# Battery_Mnitor.net
KiCad netlist of a schematic drawn in Altium Designer
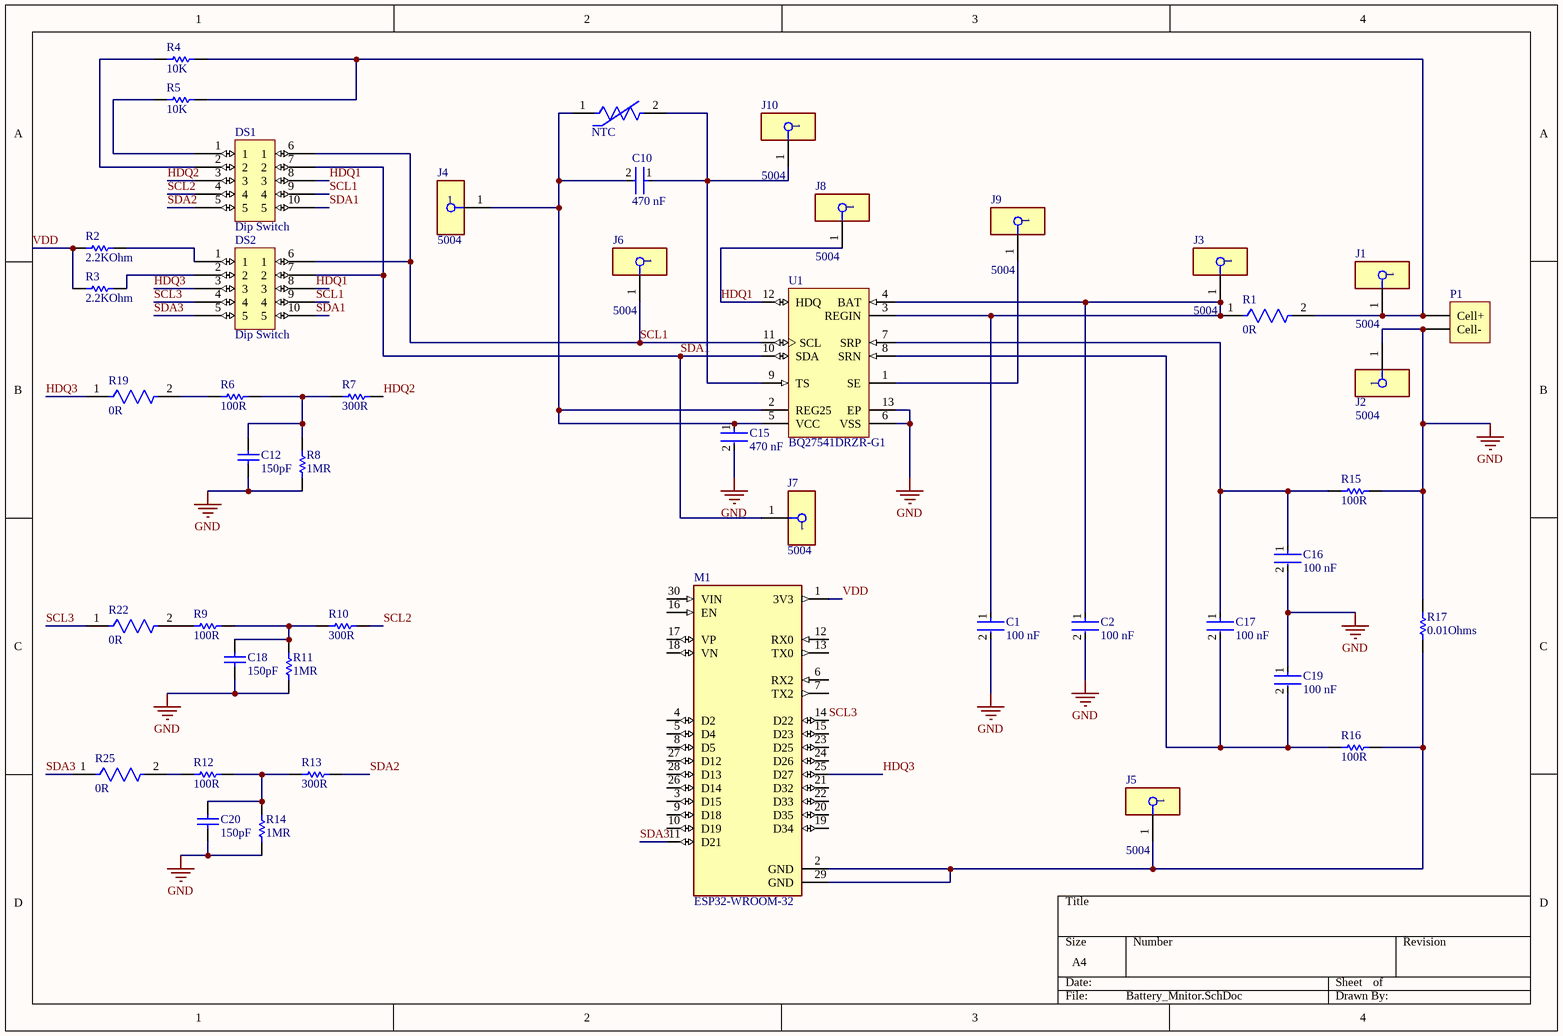
[diagram p0: Battery_Mnitor.SchDoc]

(export (version "E")
  (design (tool "Eeschema 10.0.6"))
  (components
    (comp (ref "C1")
      (value "100 nF")
      (footprint "FP-CC0402-MFG")
      (description "CC0402 100 nF X7R 10.00% 16 V")
      (fields (field (name "MANUFACTURER") "YAGEO"))
      (libsource (lib "Altium Content Vault") (part "11868f565c42a9108669ba33697ecf6"))
    )
    (comp (ref "C2")
      (value "100 nF")
      (footprint "FP-CC0402-MFG")
      (description "CC0402 100 nF X7R 10.00% 16 V")
      (fields (field (name "MANUFACTURER") "YAGEO"))
      (libsource (lib "Altium Content Vault") (part "11868f565c42a9108669ba33697ecf6"))
    )
    (comp (ref "C10")
      (value "470 nF")
      (footprint "FP-CC0402-MFG")
      (description "CC0402 470 nF X5R 10.00% 25 V")
      (fields (field (name "TOLERANCE") "0.1") (field (name "MANUFACTURER") "YAGEO"))
      (libsource (lib "Altium Content Vault") (part "11868f565c42a9108669ba33697ecf6"))
    )
    (comp (ref "C12")
      (value "150pF")
      (footprint "CAPC1005X55X25LL05T10")
      (description "50V 150pF C0G ±5% 0402 Multilayer Ceramic Capacitors MLCC - SMD/SMT ROHS")
      (fields (field (name "MANUFACTURER") "Murata") (field (name "MFR. PART #") "GRM1555C1H151JA01D"))
      (libsource (lib "Altium Content Vault") (part "CAP"))
    )
    (comp (ref "C15")
      (value "470 nF")
      (footprint "FP-CC0402-MFG")
      (description "CC0402 470 nF X5R 10.00% 25 V")
      (fields (field (name "TOLERANCE") "0.1") (field (name "MANUFACTURER") "YAGEO"))
      (libsource (lib "Altium Content Vault") (part "11868f565c42a9108669ba33697ecf6"))
    )
    (comp (ref "C16")
      (value "100 nF")
      (footprint "FP-CC0402-MFG")
      (description "CC0402 100 nF X7R 10.00% 16 V")
      (fields (field (name "MANUFACTURER") "YAGEO"))
      (libsource (lib "Altium Content Vault") (part "11868f565c42a9108669ba33697ecf6"))
    )
    (comp (ref "C17")
      (value "100 nF")
      (footprint "FP-CC0402-MFG")
      (description "CC0402 100 nF X7R 10.00% 16 V")
      (fields (field (name "MANUFACTURER") "YAGEO"))
      (libsource (lib "Altium Content Vault") (part "11868f565c42a9108669ba33697ecf6"))
    )
    (comp (ref "C18")
      (value "150pF")
      (footprint "CAPC1005X55X25LL05T10")
      (description "50V 150pF C0G ±5% 0402 Multilayer Ceramic Capacitors MLCC - SMD/SMT ROHS")
      (fields (field (name "MANUFACTURER") "Murata") (field (name "MFR. PART #") "GRM1555C1H151JA01D"))
      (libsource (lib "Altium Content Vault") (part "CAP"))
    )
    (comp (ref "C19")
      (value "100 nF")
      (footprint "FP-CC0402-MFG")
      (description "CC0402 100 nF X7R 10.00% 16 V")
      (fields (field (name "MANUFACTURER") "YAGEO"))
      (libsource (lib "Altium Content Vault") (part "11868f565c42a9108669ba33697ecf6"))
    )
    (comp (ref "C20")
      (value "150pF")
      (footprint "CAPC1005X55X25LL05T10")
      (description "50V 150pF C0G ±5% 0402 Multilayer Ceramic Capacitors MLCC - SMD/SMT ROHS")
      (fields (field (name "MANUFACTURER") "Murata") (field (name "MFR. PART #") "GRM1555C1H151JA01D"))
      (libsource (lib "Altium Content Vault") (part "CAP"))
    )
    (comp (ref "DS1")
      (value "Dip Switch")
      (footprint "DIP10")
      (description "SPST 24V 25mA Red -20℃~+70℃ 3000 Flat dial, raised type 2.54mm 6 Plugin DIP Switches ROHS")
      (fields (field (name "LCSC PART #") "C129061") (field (name "MANUFACTURER") "Korean Hroparts Elec"))
      (libsource (lib "Dip switch") (part "DS-05RP"))
    )
    (comp (ref "DS2")
      (value "Dip Switch")
      (footprint "DIP10")
      (description "SPST 24V 25mA Red -20℃~+70℃ 3000 Flat dial, raised type 2.54mm 6 Plugin DIP Switches ROHS")
      (fields (field (name "LCSC PART #") "C129061") (field (name "MANUFACTURER") "Korean Hroparts Elec"))
      (libsource (lib "Dip switch") (part "DS-05RP"))
    )
    (comp (ref "J1")
      (value "5004")
      (footprint "FP-5004-MFG")
      (description "PC TEST POINT MINIATURE YELLOW")
      (fields
        (field (name "MANUFACTURER") "Keystone")
        (field (name "OCTOPART") "https://octopart.com/5004-keystone-28591")
      )
      (libsource (lib "Altium Content Vault") (part "98815daf2f2c152b0c43f5ab9800df6"))
    )
    (comp (ref "J2")
      (value "5004")
      (footprint "FP-5004-MFG")
      (description "PC TEST POINT MINIATURE YELLOW")
      (fields
        (field (name "MANUFACTURER") "Keystone")
        (field (name "OCTOPART") "https://octopart.com/5004-keystone-28591")
      )
      (libsource (lib "") (part "98815daf2f2c152b0c43f5ab9800df6_2"))
    )
    (comp (ref "J3")
      (value "5004")
      (footprint "FP-5004-MFG")
      (description "PC TEST POINT MINIATURE YELLOW")
      (fields
        (field (name "MANUFACTURER") "Keystone")
        (field (name "OCTOPART") "https://octopart.com/5004-keystone-28591")
      )
      (libsource (lib "Altium Content Vault") (part "98815daf2f2c152b0c43f5ab9800df6"))
    )
    (comp (ref "J4")
      (value "5004")
      (footprint "FP-5004-MFG")
      (description "PC TEST POINT MINIATURE YELLOW")
      (fields
        (field (name "MANUFACTURER") "Keystone")
        (field (name "OCTOPART") "https://octopart.com/5004-keystone-28591")
      )
      (libsource (lib "") (part "98815daf2f2c152b0c43f5ab9800df6_3"))
    )
    (comp (ref "J5")
      (value "5004")
      (footprint "FP-5004-MFG")
      (description "PC TEST POINT MINIATURE YELLOW")
      (fields
        (field (name "MANUFACTURER") "Keystone")
        (field (name "OCTOPART") "https://octopart.com/5004-keystone-28591")
      )
      (libsource (lib "Altium Content Vault") (part "98815daf2f2c152b0c43f5ab9800df6"))
    )
    (comp (ref "J6")
      (value "5004")
      (footprint "FP-5004-MFG")
      (description "PC TEST POINT MINIATURE YELLOW")
      (fields
        (field (name "MANUFACTURER") "Keystone")
        (field (name "OCTOPART") "https://octopart.com/5004-keystone-28591")
      )
      (libsource (lib "Altium Content Vault") (part "98815daf2f2c152b0c43f5ab9800df6"))
    )
    (comp (ref "J7")
      (value "5004")
      (footprint "FP-5004-MFG")
      (description "PC TEST POINT MINIATURE YELLOW")
      (fields
        (field (name "MANUFACTURER") "Keystone")
        (field (name "OCTOPART") "https://octopart.com/5004-keystone-28591")
      )
      (libsource (lib "") (part "98815daf2f2c152b0c43f5ab9800df6_1"))
    )
    (comp (ref "J8")
      (value "5004")
      (footprint "FP-5004-MFG")
      (description "PC TEST POINT MINIATURE YELLOW")
      (fields
        (field (name "MANUFACTURER") "Keystone")
        (field (name "OCTOPART") "https://octopart.com/5004-keystone-28591")
      )
      (libsource (lib "Altium Content Vault") (part "98815daf2f2c152b0c43f5ab9800df6"))
    )
    (comp (ref "J9")
      (value "5004")
      (footprint "FP-5004-MFG")
      (description "PC TEST POINT MINIATURE YELLOW")
      (fields
        (field (name "MANUFACTURER") "Keystone")
        (field (name "OCTOPART") "https://octopart.com/5004-keystone-28591")
      )
      (libsource (lib "Altium Content Vault") (part "98815daf2f2c152b0c43f5ab9800df6"))
    )
    (comp (ref "J10")
      (value "5004")
      (footprint "FP-5004-MFG")
      (description "PC TEST POINT MINIATURE YELLOW")
      (fields
        (field (name "MANUFACTURER") "Keystone")
        (field (name "OCTOPART") "https://octopart.com/5004-keystone-28591")
      )
      (libsource (lib "Altium Content Vault") (part "98815daf2f2c152b0c43f5ab9800df6"))
    )
    (comp (ref "M1")
      (value "ESP32-WROOM-32")
      (footprint "ESP32-DEVKIT-V1")
      (libsource (lib "Modules") (part "ESP32-DEVKIT-V1"))
    )
    (comp (ref "NTC")
      (value "NXRT15XH103FA1B030")
      (footprint "FP-NXR_151B030-MFG")
      (description "Thermistor NTC 10kΩ ±1% 2-Pin Radial Bulk")
      (fields (field (name "TOLERANCE") "1%") (field (name "LCSC PART #") "C152559"))
      (libsource (lib "Altium Content Vault") (part "3b148a6ebabc5fb4d708a66c052d352"))
    )
    (comp (ref "P1")
      (value "Header 2H")
      (footprint "HDR1X2H")
      (description "Header, 2-Pin, Right Angle")
      (fields (field (name "PUBLISHER") "Altium Limited"))
      (libsource (lib "Miscellaneous Connectors") (part "Header 2H"))
    )
    (comp (ref "R1")
      (value "0R")
      (footprint "FP-RC0402-0_4-IPC_A")
      (description "RES SMD 0 OHM JUMPER 1/16W 0402")
      (fields (field (name "TOLERANCE") "1%") (field (name "LCSC PART #") "C106231"))
      (libsource (lib "Altium Content Vault") (part "1029c3af85768c4190bb7ad29bc67b5"))
    )
    (comp (ref "R2")
      (value "2.2KOhm")
      (footprint "RESC3116X65X40ML10T20")
      (description "Chip Resistor, 2.2 KOhm, +/- 1%, 250 mW, -55 to 155 degC, 1206 (3216 Metric), RoHS, Tape and Reel")
      (fields (field (name "MANUFACTURER") "Yageo") (field (name "TOLERANCE") "1%"))
      (libsource (lib "Altium Content Vault") (part "RES-2"))
    )
    (comp (ref "R3")
      (value "2.2KOhm")
      (footprint "RESC3116X65X40ML10T20")
      (description "Chip Resistor, 2.2 KOhm, +/- 1%, 250 mW, -55 to 155 degC, 1206 (3216 Metric), RoHS, Tape and Reel")
      (fields (field (name "MANUFACTURER") "Yageo") (field (name "TOLERANCE") "1%"))
      (libsource (lib "Altium Content Vault") (part "RES-2"))
    )
    (comp (ref "R4")
      (value "10K")
      (footprint "RESC1005X40X25LL05T10")
      (fields
        (field (name "MANUFACTURER") "Yageo / Phycomp")
        (field (name "LCSC PART #") "C60490")
        (field (name "MFR. PART #") "RC0402FR-0710KL")
      )
      (libsource (lib "Altium Content Vault") (part "RES"))
    )
    (comp (ref "R5")
      (value "10K")
      (footprint "RESC1005X40X25LL05T10")
      (fields
        (field (name "MANUFACTURER") "Yageo / Phycomp")
        (field (name "LCSC PART #") "C60490")
        (field (name "MFR. PART #") "RC0402FR-0710KL")
      )
      (libsource (lib "Altium Content Vault") (part "RES"))
    )
    (comp (ref "R6")
      (value "100R")
      (footprint "RESC1005X40X25ML05T10")
      (fields
        (field (name "MFR. PART #") "RC0402FR-07100RL")
        (field (name "MANUFACTURER") "Yageo / Phycomp")
        (field (name "LCSC PART #") "C106232")
      )
      (libsource (lib "Altium Content Vault") (part "RES"))
    )
    (comp (ref "R7")
      (value "300R")
      (footprint "RESC1005X40X25LL05T10")
      (fields
        (field (name "MFR. PART #") "RC0402FR-07300RL")
        (field (name "MANUFACTURER") "Yageo / Phycomp")
        (field (name "LCSC PART #") "C138010")
      )
      (libsource (lib "Altium Content Vault") (part "RES"))
    )
    (comp (ref "R8")
      (value "1MR")
      (footprint "RESC1005X40X25NL05T10")
      (description "62.5mW 50V ±100ppm/℃ ±1% -55℃~+155℃ 1MΩ 0402 Chip Resistor - Surface Mount ROHS")
      (fields (field (name "MANUFACTURER") "Yageo / Phycomp") (field (name "MFR. PART #") "RC0402FR-071ML"))
      (libsource (lib "Altium Content Vault") (part "RES"))
    )
    (comp (ref "R9")
      (value "100R")
      (footprint "RESC1005X40X25ML05T10")
      (fields
        (field (name "MFR. PART #") "RC0402FR-07100RL")
        (field (name "MANUFACTURER") "Yageo / Phycomp")
        (field (name "LCSC PART #") "C106232")
      )
      (libsource (lib "Altium Content Vault") (part "RES"))
    )
    (comp (ref "R10")
      (value "300R")
      (footprint "RESC1005X40X25LL05T10")
      (fields
        (field (name "MFR. PART #") "RC0402FR-07300RL")
        (field (name "MANUFACTURER") "Yageo / Phycomp")
        (field (name "LCSC PART #") "C138010")
      )
      (libsource (lib "Altium Content Vault") (part "RES"))
    )
    (comp (ref "R11")
      (value "1MR")
      (footprint "RESC1005X40X25NL05T10")
      (description "62.5mW 50V ±100ppm/℃ ±1% -55℃~+155℃ 1MΩ 0402 Chip Resistor - Surface Mount ROHS")
      (fields (field (name "MANUFACTURER") "Yageo / Phycomp") (field (name "MFR. PART #") "RC0402FR-071ML"))
      (libsource (lib "Altium Content Vault") (part "RES"))
    )
    (comp (ref "R12")
      (value "100R")
      (footprint "RESC1005X40X25ML05T10")
      (fields
        (field (name "MFR. PART #") "RC0402FR-07100RL")
        (field (name "MANUFACTURER") "Yageo / Phycomp")
        (field (name "LCSC PART #") "C106232")
      )
      (libsource (lib "Altium Content Vault") (part "RES"))
    )
    (comp (ref "R13")
      (value "300R")
      (footprint "RESC1005X40X25LL05T10")
      (fields
        (field (name "MFR. PART #") "RC0402FR-07300RL")
        (field (name "MANUFACTURER") "Yageo / Phycomp")
        (field (name "LCSC PART #") "C138010")
      )
      (libsource (lib "Altium Content Vault") (part "RES"))
    )
    (comp (ref "R14")
      (value "1MR")
      (footprint "RESC1005X40X25NL05T10")
      (description "62.5mW 50V ±100ppm/℃ ±1% -55℃~+155℃ 1MΩ 0402 Chip Resistor - Surface Mount ROHS")
      (fields (field (name "MANUFACTURER") "Yageo / Phycomp") (field (name "MFR. PART #") "RC0402FR-071ML"))
      (libsource (lib "Altium Content Vault") (part "RES"))
    )
    (comp (ref "R15")
      (value "100R")
      (footprint "RESC1005X40X25ML05T10")
      (fields
        (field (name "MFR. PART #") "RC0402FR-07100RL")
        (field (name "MANUFACTURER") "Yageo / Phycomp")
        (field (name "LCSC PART #") "C106232")
      )
      (libsource (lib "Altium Content Vault") (part "RES"))
    )
    (comp (ref "R16")
      (value "100R")
      (footprint "RESC1005X40X25ML05T10")
      (fields
        (field (name "MFR. PART #") "RC0402FR-07100RL")
        (field (name "MANUFACTURER") "Yageo / Phycomp")
        (field (name "LCSC PART #") "C106232")
      )
      (libsource (lib "Altium Content Vault") (part "RES"))
    )
    (comp (ref "R17")
      (value "0.01Ohms")
      (footprint "RESC5125X89X51LL25T25")
      (description "Chip Resistor, 10 mOhm, +/- 1%, 0.5 W, -65 to 170 degC, 2010 (5025 Metric), RoHS, Tape and Reel")
      (fields (field (name "MANUFACTURER") "Vishay") (field (name "TOLERANCE") "1%"))
      (libsource (lib "Altium Content Vault") (part "RES-2"))
    )
    (comp (ref "R19")
      (value "0R")
      (footprint "FP-RC0402-0_4-IPC_A")
      (description "RES SMD 0 OHM JUMPER 1/16W 0402")
      (fields (field (name "TOLERANCE") "1%") (field (name "LCSC PART #") "C106231"))
      (libsource (lib "Altium Content Vault") (part "1029c3af85768c4190bb7ad29bc67b5"))
    )
    (comp (ref "R22")
      (value "0R")
      (footprint "FP-RC0402-0_4-IPC_A")
      (description "RES SMD 0 OHM JUMPER 1/16W 0402")
      (fields (field (name "TOLERANCE") "1%") (field (name "LCSC PART #") "C106231"))
      (libsource (lib "Altium Content Vault") (part "1029c3af85768c4190bb7ad29bc67b5"))
    )
    (comp (ref "R25")
      (value "0R")
      (footprint "FP-RC0402-0_4-IPC_A")
      (description "RES SMD 0 OHM JUMPER 1/16W 0402")
      (fields (field (name "TOLERANCE") "1%") (field (name "LCSC PART #") "C106231"))
      (libsource (lib "Altium Content Vault") (part "1029c3af85768c4190bb7ad29bc67b5"))
    )
    (comp (ref "U1")
      (value "BQ27541DRZR-G1")
      (footprint "DRZ0012A_V")
      (fields (field (name "MANUFACTURER") "Texas Instruments"))
      (libsource (lib "Altium Content Vault") (part "TI-BQ27541-G1DRZ12-1950X2450TP"))
    )
  )
  (nets
    (net (code "1") (name "/HDQ1") (class "Default")
      (node (ref "DS1") (pin "8") (pinfunction "3_8") (pintype "bidirectional"))
      (node (ref "DS2") (pin "8") (pinfunction "3_8") (pintype "bidirectional"))
      (node (ref "J8") (pin "1") (pinfunction "1_1") (pintype "passive"))
      (node (ref "U1") (pin "12") (pinfunction "HDQ_12") (pintype "bidirectional"))
    )
    (net (code "2") (name "/HDQ2") (class "Default")
      (node (ref "DS1") (pin "3") (pinfunction "3_3") (pintype "bidirectional"))
      (node (ref "R7") (pin "2") (pinfunction "2_2") (pintype "passive"))
    )
    (net (code "3") (name "/HDQ3") (class "Default")
      (node (ref "DS2") (pin "3") (pinfunction "3_3") (pintype "bidirectional"))
      (node (ref "M1") (pin "25") (pinfunction "D27_25") (pintype "bidirectional"))
      (node (ref "R19") (pin "1") (pinfunction "1_1") (pintype "passive"))
    )
    (net (code "4") (name "/SCL1") (class "Default")
      (node (ref "DS1") (pin "6") (pinfunction "1_6") (pintype "bidirectional"))
      (node (ref "DS1") (pin "9") (pinfunction "4_9") (pintype "bidirectional"))
      (node (ref "DS2") (pin "6") (pinfunction "1_6") (pintype "bidirectional"))
      (node (ref "DS2") (pin "9") (pinfunction "4_9") (pintype "bidirectional"))
      (node (ref "J6") (pin "1") (pinfunction "1_1") (pintype "passive"))
      (node (ref "U1") (pin "11") (pinfunction "SCL_11") (pintype "bidirectional"))
    )
    (net (code "5") (name "/SCL2") (class "Default")
      (node (ref "DS1") (pin "4") (pinfunction "4_4") (pintype "bidirectional"))
      (node (ref "R10") (pin "2") (pinfunction "2_2") (pintype "passive"))
    )
    (net (code "6") (name "/SCL3") (class "Default")
      (node (ref "DS2") (pin "4") (pinfunction "4_4") (pintype "bidirectional"))
      (node (ref "M1") (pin "14") (pinfunction "D22_14") (pintype "bidirectional"))
      (node (ref "R22") (pin "1") (pinfunction "1_1") (pintype "passive"))
    )
    (net (code "7") (name "/SDA1") (class "Default")
      (node (ref "DS1") (pin "10") (pinfunction "5_10") (pintype "bidirectional"))
      (node (ref "DS1") (pin "7") (pinfunction "2_7") (pintype "bidirectional"))
      (node (ref "DS2") (pin "10") (pinfunction "5_10") (pintype "bidirectional"))
      (node (ref "DS2") (pin "7") (pinfunction "2_7") (pintype "bidirectional"))
      (node (ref "J7") (pin "1") (pinfunction "1_1") (pintype "passive"))
      (node (ref "U1") (pin "10") (pinfunction "SDA_10") (pintype "bidirectional"))
    )
    (net (code "8") (name "/SDA2") (class "Default")
      (node (ref "DS1") (pin "5") (pinfunction "5_5") (pintype "bidirectional"))
      (node (ref "R13") (pin "2") (pinfunction "2_2") (pintype "passive"))
    )
    (net (code "9") (name "/SDA3") (class "Default")
      (node (ref "DS2") (pin "5") (pinfunction "5_5") (pintype "bidirectional"))
      (node (ref "M1") (pin "11") (pinfunction "D21_11") (pintype "bidirectional"))
      (node (ref "R25") (pin "1") (pinfunction "1_1") (pintype "passive"))
    )
    (net (code "10") (name "/VDD") (class "Default")
      (node (ref "M1") (pin "1") (pinfunction "3V3_1") (pintype "output"))
      (node (ref "R2") (pin "1") (pinfunction "1_1") (pintype "passive"))
      (node (ref "R3") (pin "1") (pinfunction "1_1") (pintype "passive"))
    )
    (net (code "11") (name "GND") (class "Default")
      (node (ref "C1") (pin "2") (pinfunction "2_2") (pintype "passive"))
      (node (ref "C12") (pin "1") (pinfunction "1_1") (pintype "passive"))
      (node (ref "C15") (pin "2") (pinfunction "2_2") (pintype "passive"))
      (node (ref "C16") (pin "2") (pinfunction "2_2") (pintype "passive"))
      (node (ref "C18") (pin "1") (pinfunction "1_1") (pintype "passive"))
      (node (ref "C19") (pin "1") (pinfunction "1_1") (pintype "passive"))
      (node (ref "C2") (pin "2") (pinfunction "2_2") (pintype "passive"))
      (node (ref "C20") (pin "1") (pinfunction "1_1") (pintype "passive"))
      (node (ref "J2") (pin "1") (pinfunction "1_1") (pintype "passive"))
      (node (ref "P1") (pin "2") (pinfunction "Cell-_2") (pintype "passive"))
      (node (ref "R11") (pin "1") (pinfunction "1_1") (pintype "passive"))
      (node (ref "R14") (pin "1") (pinfunction "1_1") (pintype "passive"))
      (node (ref "R15") (pin "2") (pinfunction "2_2") (pintype "passive"))
      (node (ref "R17") (pin "2") (pinfunction "2_2") (pintype "passive"))
      (node (ref "R8") (pin "1") (pinfunction "1_1") (pintype "passive"))
      (node (ref "U1") (pin "13") (pinfunction "EP_13") (pintype "passive"))
      (node (ref "U1") (pin "6") (pinfunction "VSS_6") (pintype "power_in"))
    )
    (net (code "12") (name "Net-(C12-Pad2)") (class "Default")
      (node (ref "C12") (pin "2") (pinfunction "2_2") (pintype "passive"))
      (node (ref "R6") (pin "2") (pinfunction "2_2") (pintype "passive"))
      (node (ref "R7") (pin "1") (pinfunction "1_1") (pintype "passive"))
      (node (ref "R8") (pin "2") (pinfunction "2_2") (pintype "passive"))
    )
    (net (code "13") (name "Net-(C18-Pad2)") (class "Default")
      (node (ref "C18") (pin "2") (pinfunction "2_2") (pintype "passive"))
      (node (ref "R10") (pin "1") (pinfunction "1_1") (pintype "passive"))
      (node (ref "R11") (pin "2") (pinfunction "2_2") (pintype "passive"))
      (node (ref "R9") (pin "2") (pinfunction "2_2") (pintype "passive"))
    )
    (net (code "14") (name "Net-(C20-Pad2)") (class "Default")
      (node (ref "C20") (pin "2") (pinfunction "2_2") (pintype "passive"))
      (node (ref "R12") (pin "2") (pinfunction "2_2") (pintype "passive"))
      (node (ref "R13") (pin "1") (pinfunction "1_1") (pintype "passive"))
      (node (ref "R14") (pin "2") (pinfunction "2_2") (pintype "passive"))
    )
    (net (code "15") (name "Net-(DS1-Pad1)") (class "Default")
      (node (ref "DS1") (pin "1") (pinfunction "1_1") (pintype "bidirectional"))
      (node (ref "R5") (pin "2") (pinfunction "2_2") (pintype "passive"))
    )
    (net (code "16") (name "Net-(DS1-Pad2)") (class "Default")
      (node (ref "DS1") (pin "2") (pinfunction "2_2") (pintype "bidirectional"))
      (node (ref "R4") (pin "2") (pinfunction "2_2") (pintype "passive"))
    )
    (net (code "17") (name "Net-(DS2-Pad1)") (class "Default")
      (node (ref "DS2") (pin "1") (pinfunction "1_1") (pintype "bidirectional"))
      (node (ref "R2") (pin "2") (pinfunction "2_2") (pintype "passive"))
    )
    (net (code "18") (name "Net-(DS2-Pad2)") (class "Default")
      (node (ref "DS2") (pin "2") (pinfunction "2_2") (pintype "bidirectional"))
      (node (ref "R3") (pin "2") (pinfunction "2_2") (pintype "passive"))
    )
    (net (code "19") (name "Net-(J5-Pad1)") (class "Default")
      (node (ref "J5") (pin "1") (pinfunction "1_1") (pintype "passive"))
      (node (ref "M1") (pin "2") (pinfunction "GND_2") (pintype "power_in"))
      (node (ref "M1") (pin "29") (pinfunction "GND_29") (pintype "power_in"))
      (node (ref "R16") (pin "2") (pinfunction "2_2") (pintype "passive"))
      (node (ref "R17") (pin "1") (pinfunction "1_1") (pintype "passive"))
    )
    (net (code "20") (name "Net-(P1-Cell+)") (class "Default")
      (node (ref "J1") (pin "1") (pinfunction "1_1") (pintype "passive"))
      (node (ref "P1") (pin "1") (pinfunction "Cell+_1") (pintype "passive"))
      (node (ref "R1") (pin "2") (pinfunction "2_2") (pintype "passive"))
      (node (ref "R4") (pin "1") (pinfunction "1_1") (pintype "passive"))
      (node (ref "R5") (pin "1") (pinfunction "1_1") (pintype "passive"))
    )
    (net (code "21") (name "Net-(R12-Pad1)") (class "Default")
      (node (ref "R12") (pin "1") (pinfunction "1_1") (pintype "passive"))
      (node (ref "R25") (pin "2") (pinfunction "2_2") (pintype "passive"))
    )
    (net (code "22") (name "Net-(R19-Pad2)") (class "Default")
      (node (ref "R19") (pin "2") (pinfunction "2_2") (pintype "passive"))
      (node (ref "R6") (pin "1") (pinfunction "1_1") (pintype "passive"))
    )
    (net (code "23") (name "Net-(R22-Pad2)") (class "Default")
      (node (ref "R22") (pin "2") (pinfunction "2_2") (pintype "passive"))
      (node (ref "R9") (pin "1") (pinfunction "1_1") (pintype "passive"))
    )
    (net (code "24") (name "Net-(U1-BAT)") (class "Default")
      (node (ref "C1") (pin "1") (pinfunction "1_1") (pintype "passive"))
      (node (ref "C2") (pin "1") (pinfunction "1_1") (pintype "passive"))
      (node (ref "J3") (pin "1") (pinfunction "1_1") (pintype "passive"))
      (node (ref "R1") (pin "1") (pinfunction "1_1") (pintype "passive"))
      (node (ref "U1") (pin "3") (pinfunction "REGIN_3") (pintype "power_in"))
      (node (ref "U1") (pin "4") (pinfunction "BAT_4") (pintype "input"))
    )
    (net (code "25") (name "Net-(U1-REG25)") (class "Default")
      (node (ref "C10") (pin "2") (pinfunction "2_2") (pintype "passive"))
      (node (ref "C15") (pin "1") (pinfunction "1_1") (pintype "passive"))
      (node (ref "J4") (pin "1") (pinfunction "1_1") (pintype "passive"))
      (node (ref "NTC") (pin "1") (pinfunction "1_1") (pintype "passive"))
      (node (ref "U1") (pin "2") (pinfunction "REG25_2") (pintype "power_in"))
      (node (ref "U1") (pin "5") (pinfunction "VCC_5") (pintype "power_in"))
    )
    (net (code "26") (name "Net-(U1-SE)") (class "Default")
      (node (ref "J9") (pin "1") (pinfunction "1_1") (pintype "passive"))
      (node (ref "U1") (pin "1") (pinfunction "SE_1") (pintype "tri_state"))
    )
    (net (code "27") (name "Net-(U1-SRN)") (class "Default")
      (node (ref "C17") (pin "2") (pinfunction "2_2") (pintype "passive"))
      (node (ref "C19") (pin "2") (pinfunction "2_2") (pintype "passive"))
      (node (ref "R16") (pin "1") (pinfunction "1_1") (pintype "passive"))
      (node (ref "U1") (pin "8") (pinfunction "SRN_8") (pintype "input"))
    )
    (net (code "28") (name "Net-(U1-SRP)") (class "Default")
      (node (ref "C16") (pin "1") (pinfunction "1_1") (pintype "passive"))
      (node (ref "C17") (pin "1") (pinfunction "1_1") (pintype "passive"))
      (node (ref "R15") (pin "1") (pinfunction "1_1") (pintype "passive"))
      (node (ref "U1") (pin "7") (pinfunction "SRP_7") (pintype "input"))
    )
    (net (code "29") (name "Net-(U1-TS)") (class "Default")
      (node (ref "C10") (pin "1") (pinfunction "1_1") (pintype "passive"))
      (node (ref "J10") (pin "1") (pinfunction "1_1") (pintype "passive"))
      (node (ref "NTC") (pin "2") (pinfunction "2_2") (pintype "passive"))
      (node (ref "U1") (pin "9") (pinfunction "TS_9") (pintype "input"))
    )
    (net (code "30") (name "unconnected-(M1-D2-Pad4)") (class "Default")
      (node (ref "M1") (pin "4") (pinfunction "D2_4") (pintype "bidirectional"))
    )
    (net (code "31") (name "unconnected-(M1-D4-Pad5)") (class "Default")
      (node (ref "M1") (pin "5") (pinfunction "D4_5") (pintype "bidirectional"))
    )
    (net (code "32") (name "unconnected-(M1-D5-Pad8)") (class "Default")
      (node (ref "M1") (pin "8") (pinfunction "D5_8") (pintype "bidirectional"))
    )
    (net (code "33") (name "unconnected-(M1-D12-Pad27)") (class "Default")
      (node (ref "M1") (pin "27") (pinfunction "D12_27") (pintype "bidirectional"))
    )
    (net (code "34") (name "unconnected-(M1-D13-Pad28)") (class "Default")
      (node (ref "M1") (pin "28") (pinfunction "D13_28") (pintype "bidirectional"))
    )
    (net (code "35") (name "unconnected-(M1-D14-Pad26)") (class "Default")
      (node (ref "M1") (pin "26") (pinfunction "D14_26") (pintype "bidirectional"))
    )
    (net (code "36") (name "unconnected-(M1-D15-Pad3)") (class "Default")
      (node (ref "M1") (pin "3") (pinfunction "D15_3") (pintype "bidirectional"))
    )
    (net (code "37") (name "unconnected-(M1-D18-Pad9)") (class "Default")
      (node (ref "M1") (pin "9") (pinfunction "D18_9") (pintype "bidirectional"))
    )
    (net (code "38") (name "unconnected-(M1-D19-Pad10)") (class "Default")
      (node (ref "M1") (pin "10") (pinfunction "D19_10") (pintype "bidirectional"))
    )
    (net (code "39") (name "unconnected-(M1-D23-Pad15)") (class "Default")
      (node (ref "M1") (pin "15") (pinfunction "D23_15") (pintype "bidirectional"))
    )
    (net (code "40") (name "unconnected-(M1-D25-Pad23)") (class "Default")
      (node (ref "M1") (pin "23") (pinfunction "D25_23") (pintype "bidirectional"))
    )
    (net (code "41") (name "unconnected-(M1-D26-Pad24)") (class "Default")
      (node (ref "M1") (pin "24") (pinfunction "D26_24") (pintype "bidirectional"))
    )
    (net (code "42") (name "unconnected-(M1-D32-Pad21)") (class "Default")
      (node (ref "M1") (pin "21") (pinfunction "D32_21") (pintype "bidirectional"))
    )
    (net (code "43") (name "unconnected-(M1-D33-Pad22)") (class "Default")
      (node (ref "M1") (pin "22") (pinfunction "D33_22") (pintype "bidirectional"))
    )
    (net (code "44") (name "unconnected-(M1-D34-Pad19)") (class "Default")
      (node (ref "M1") (pin "19") (pinfunction "D34_19") (pintype "bidirectional"))
    )
    (net (code "45") (name "unconnected-(M1-D35-Pad20)") (class "Default")
      (node (ref "M1") (pin "20") (pinfunction "D35_20") (pintype "bidirectional"))
    )
    (net (code "46") (name "unconnected-(M1-EN-Pad16)") (class "Default")
      (node (ref "M1") (pin "16") (pinfunction "EN_16") (pintype "input"))
    )
    (net (code "47") (name "unconnected-(M1-RX0-Pad12)") (class "Default")
      (node (ref "M1") (pin "12") (pinfunction "RX0_12") (pintype "input"))
    )
    (net (code "48") (name "unconnected-(M1-RX2-Pad6)") (class "Default")
      (node (ref "M1") (pin "6") (pinfunction "RX2_6") (pintype "input"))
    )
    (net (code "49") (name "unconnected-(M1-TX0-Pad13)") (class "Default")
      (node (ref "M1") (pin "13") (pinfunction "TX0_13") (pintype "output"))
    )
    (net (code "50") (name "unconnected-(M1-TX2-Pad7)") (class "Default")
      (node (ref "M1") (pin "7") (pinfunction "TX2_7") (pintype "output"))
    )
    (net (code "51") (name "unconnected-(M1-VIN-Pad30)") (class "Default")
      (node (ref "M1") (pin "30") (pinfunction "VIN_30") (pintype "input"))
    )
    (net (code "52") (name "unconnected-(M1-VN-Pad18)") (class "Default")
      (node (ref "M1") (pin "18") (pinfunction "VN_18") (pintype "bidirectional"))
    )
    (net (code "53") (name "unconnected-(M1-VP-Pad17)") (class "Default")
      (node (ref "M1") (pin "17") (pinfunction "VP_17") (pintype "bidirectional"))
    )
  )
)
